# AuxiliaryPowerSupply.net
KiCad netlist of a schematic drawn in Altium Designer
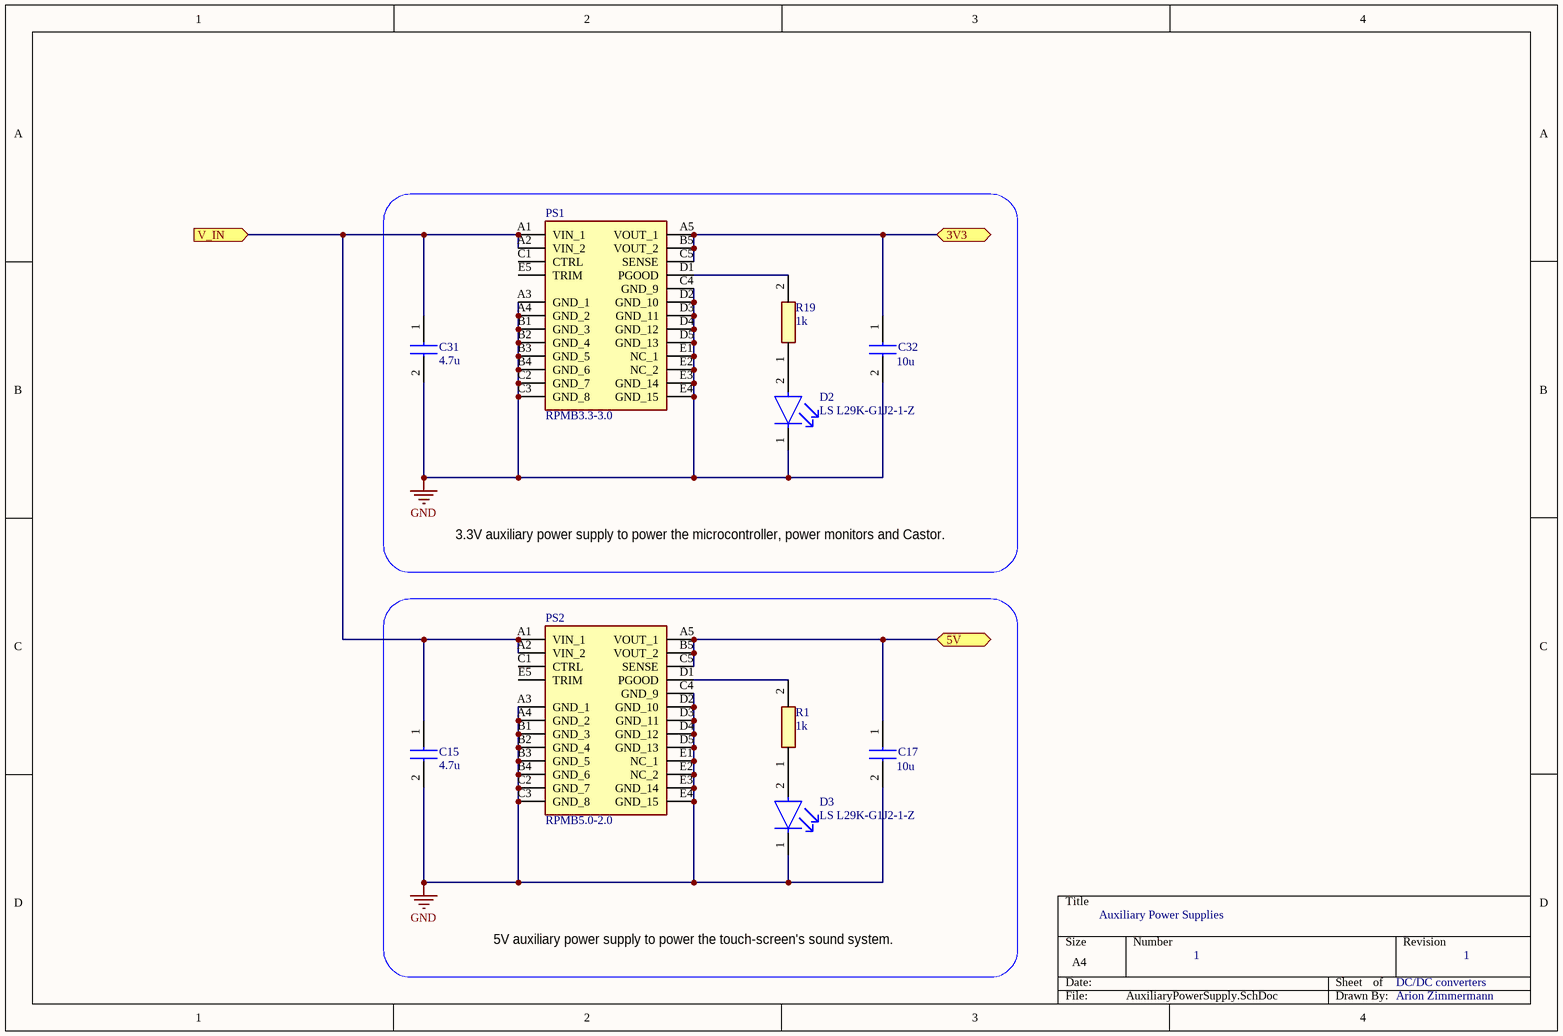
[diagram p0: AuxiliaryPowerSupply.SchDoc]

(export (version "E")
  (design (tool "Eeschema 10.0.6"))
  (components
    (comp (ref "C15")
      (value "4.7u")
      (footprint "SamacSys:CAPC5750X310N")
      (description "Capacitor")
      (fields
        (field (name "MANUFACTURER_PART_NUMBER") "C5750X7R2A475K230KA")
        (field (name "MOUSER PART NUMBER") "810-C5750X7R2A475K")
      )
      (libsource (lib "CarrierBoard") (part "C5750X7R2A475K230KA"))
    )
    (comp (ref "C17")
      (value "10u")
      (footprint "SamacSys:C1206")
      (description "Capacitor")
      (fields
        (field (name "MANUFACTURER_PART_NUMBER") "C1206C106K4RACTU")
        (field (name "MOUSER PART NUMBER") "80-C1206C106K4R")
      )
      (libsource (lib "SamacSys") (part "C1206C106K4RACTU"))
    )
    (comp (ref "C31")
      (value "4.7u")
      (footprint "SamacSys:CAPC5750X310N")
      (description "Capacitor")
      (fields
        (field (name "MANUFACTURER_PART_NUMBER") "C5750X7R2A475K230KA")
        (field (name "MOUSER PART NUMBER") "810-C5750X7R2A475K")
      )
      (libsource (lib "CarrierBoard") (part "C5750X7R2A475K230KA"))
    )
    (comp (ref "C32")
      (value "10u")
      (footprint "SamacSys:C1206")
      (description "Capacitor")
      (fields
        (field (name "MANUFACTURER_PART_NUMBER") "C1206C106K4RACTU")
        (field (name "MOUSER PART NUMBER") "80-C1206C106K4R")
      )
      (libsource (lib "SamacSys") (part "C1206C106K4RACTU"))
    )
    (comp (ref "D2")
      (value "LS L29K-G1J2-1-Z")
      (footprint "FP-LS_L29K-MFG")
      (description "LED RED DIFFUSED 0603 SMD")
      (fields
        (field (name "MANUFACTURER") "Osram Opto")
        (field (name "OCTOPART") "https://octopart.com/ls+l29k-g1j2-1-z-osram+opto-31093939")
      )
      (libsource (lib "Altium Content Vault") (part "8706943c75ba83719d021d2fdc84c58"))
    )
    (comp (ref "D3")
      (value "LS L29K-G1J2-1-Z")
      (footprint "FP-LS_L29K-MFG")
      (description "LED RED DIFFUSED 0603 SMD")
      (fields
        (field (name "MANUFACTURER") "Osram Opto")
        (field (name "OCTOPART") "https://octopart.com/ls+l29k-g1j2-1-z-osram+opto-31093939")
      )
      (libsource (lib "Altium Content Vault") (part "8706943c75ba83719d021d2fdc84c58"))
    )
    (comp (ref "PS1")
      (value "RPMB3.3-3.0")
      (footprint "CarrierBoard:RPMB5030")
      (description "Power Supply")
      (fields
        (field (name "MANUFACTURER_PART_NUMBER") "RPMB5.0-3.0")
        (field (name "MOUSER PART NUMBER") "919-RPMB5.0-3.0")
      )
      (libsource (lib "*") (part "RPMB5.0-3.0"))
    )
    (comp (ref "PS2")
      (value "RPMB5.0-2.0")
      (footprint "RPMB5020")
      (description "Power Supply")
      (libsource (lib "SamacSys") (part "RPMB5.0-2.0"))
    )
    (comp (ref "R1")
      (value "1k")
      (footprint "SamacSys:RESC1608X55N")
      (description "Resistor")
      (fields
        (field (name "MANUFACTURER_PART_NUMBER") "CRCW06031K00JNEAC")
        (field (name "MOUSER PART NUMBER") "71-CRCW06031K00JNEAC")
      )
      (libsource (lib "CarrierBoard") (part "CRCW06031K00JNEAC"))
    )
    (comp (ref "R19")
      (value "1k")
      (footprint "SamacSys:RESC1608X55N")
      (description "Resistor")
      (fields
        (field (name "MANUFACTURER_PART_NUMBER") "CRCW06031K00JNEAC")
        (field (name "MOUSER PART NUMBER") "71-CRCW06031K00JNEAC")
      )
      (libsource (lib "CarrierBoard") (part "CRCW06031K00JNEAC"))
    )
  )
  (nets
    (net (code "1") (name "/3V3") (class "Default")
      (node (ref "C32") (pin "1") (pinfunction "1_1") (pintype "passive"))
      (node (ref "PS1") (pin "A5") (pinfunction "VOUT_1_A5") (pintype "passive"))
      (node (ref "PS1") (pin "B5") (pinfunction "VOUT_2_B5") (pintype "passive"))
      (node (ref "PS1") (pin "C5") (pinfunction "SENSE_C5") (pintype "passive"))
    )
    (net (code "2") (name "/5V") (class "Default")
      (node (ref "C17") (pin "1") (pinfunction "1_1") (pintype "passive"))
      (node (ref "PS2") (pin "A5") (pinfunction "VOUT_1_A5") (pintype "passive"))
      (node (ref "PS2") (pin "B5") (pinfunction "VOUT_2_B5") (pintype "passive"))
      (node (ref "PS2") (pin "C5") (pinfunction "SENSE_C5") (pintype "passive"))
    )
    (net (code "3") (name "/V_IN") (class "Default")
      (node (ref "C15") (pin "1") (pinfunction "1_1") (pintype "passive"))
      (node (ref "C31") (pin "1") (pinfunction "1_1") (pintype "passive"))
      (node (ref "PS1") (pin "A1") (pinfunction "VIN_1_A1") (pintype "passive"))
      (node (ref "PS1") (pin "A2") (pinfunction "VIN_2_A2") (pintype "passive"))
      (node (ref "PS2") (pin "A1") (pinfunction "VIN_1_A1") (pintype "passive"))
      (node (ref "PS2") (pin "A2") (pinfunction "VIN_2_A2") (pintype "passive"))
    )
    (net (code "4") (name "GND") (class "Default")
      (node (ref "C15") (pin "2") (pinfunction "2_2") (pintype "passive"))
      (node (ref "C17") (pin "2") (pinfunction "2_2") (pintype "passive"))
      (node (ref "C31") (pin "2") (pinfunction "2_2") (pintype "passive"))
      (node (ref "C32") (pin "2") (pinfunction "2_2") (pintype "passive"))
      (node (ref "D2") (pin "1") (pinfunction "C_1") (pintype "passive"))
      (node (ref "D3") (pin "1") (pinfunction "C_1") (pintype "passive"))
      (node (ref "PS1") (pin "A3") (pinfunction "GND_1_A3") (pintype "passive"))
      (node (ref "PS1") (pin "A4") (pinfunction "GND_2_A4") (pintype "passive"))
      (node (ref "PS1") (pin "B1") (pinfunction "GND_3_B1") (pintype "passive"))
      (node (ref "PS1") (pin "B2") (pinfunction "GND_4_B2") (pintype "passive"))
      (node (ref "PS1") (pin "B3") (pinfunction "GND_5_B3") (pintype "passive"))
      (node (ref "PS1") (pin "B4") (pinfunction "GND_6_B4") (pintype "passive"))
      (node (ref "PS1") (pin "C2") (pinfunction "GND_7_C2") (pintype "passive"))
      (node (ref "PS1") (pin "C3") (pinfunction "GND_8_C3") (pintype "passive"))
      (node (ref "PS1") (pin "C4") (pinfunction "GND_9_C4") (pintype "passive"))
      (node (ref "PS1") (pin "D2") (pinfunction "GND_10_D2") (pintype "passive"))
      (node (ref "PS1") (pin "D3") (pinfunction "GND_11_D3") (pintype "passive"))
      (node (ref "PS1") (pin "D4") (pinfunction "GND_12_D4") (pintype "passive"))
      (node (ref "PS1") (pin "D5") (pinfunction "GND_13_D5") (pintype "passive"))
      (node (ref "PS1") (pin "E1") (pinfunction "NC_1_E1") (pintype "passive"))
      (node (ref "PS1") (pin "E2") (pinfunction "NC_2_E2") (pintype "passive"))
      (node (ref "PS1") (pin "E3") (pinfunction "GND_14_E3") (pintype "passive"))
      (node (ref "PS1") (pin "E4") (pinfunction "GND_15_E4") (pintype "passive"))
      (node (ref "PS2") (pin "A3") (pinfunction "GND_1_A3") (pintype "passive"))
      (node (ref "PS2") (pin "A4") (pinfunction "GND_2_A4") (pintype "passive"))
      (node (ref "PS2") (pin "B1") (pinfunction "GND_3_B1") (pintype "passive"))
      (node (ref "PS2") (pin "B2") (pinfunction "GND_4_B2") (pintype "passive"))
      (node (ref "PS2") (pin "B3") (pinfunction "GND_5_B3") (pintype "passive"))
      (node (ref "PS2") (pin "B4") (pinfunction "GND_6_B4") (pintype "passive"))
      (node (ref "PS2") (pin "C2") (pinfunction "GND_7_C2") (pintype "passive"))
      (node (ref "PS2") (pin "C3") (pinfunction "GND_8_C3") (pintype "passive"))
      (node (ref "PS2") (pin "C4") (pinfunction "GND_9_C4") (pintype "passive"))
      (node (ref "PS2") (pin "D2") (pinfunction "GND_10_D2") (pintype "passive"))
      (node (ref "PS2") (pin "D3") (pinfunction "GND_11_D3") (pintype "passive"))
      (node (ref "PS2") (pin "D4") (pinfunction "GND_12_D4") (pintype "passive"))
      (node (ref "PS2") (pin "D5") (pinfunction "GND_13_D5") (pintype "passive"))
      (node (ref "PS2") (pin "E1") (pinfunction "NC_1_E1") (pintype "passive"))
      (node (ref "PS2") (pin "E2") (pinfunction "NC_2_E2") (pintype "passive"))
      (node (ref "PS2") (pin "E3") (pinfunction "GND_14_E3") (pintype "passive"))
      (node (ref "PS2") (pin "E4") (pinfunction "GND_15_E4") (pintype "passive"))
    )
    (net (code "5") (name "Net-(D2-A)") (class "Default")
      (node (ref "D2") (pin "2") (pinfunction "A_2") (pintype "passive"))
      (node (ref "R19") (pin "1") (pinfunction "1_1") (pintype "passive"))
    )
    (net (code "6") (name "Net-(D3-A)") (class "Default")
      (node (ref "D3") (pin "2") (pinfunction "A_2") (pintype "passive"))
      (node (ref "R1") (pin "1") (pinfunction "1_1") (pintype "passive"))
    )
    (net (code "7") (name "Net-(PS1-PGOOD)") (class "Default")
      (node (ref "PS1") (pin "D1") (pinfunction "PGOOD_D1") (pintype "passive"))
      (node (ref "R19") (pin "2") (pinfunction "2_2") (pintype "passive"))
    )
    (net (code "8") (name "Net-(PS2-PGOOD)") (class "Default")
      (node (ref "PS2") (pin "D1") (pinfunction "PGOOD_D1") (pintype "passive"))
      (node (ref "R1") (pin "2") (pinfunction "2_2") (pintype "passive"))
    )
    (net (code "9") (name "unconnected-(PS1-CTRL-PadC1)") (class "Default")
      (node (ref "PS1") (pin "C1") (pinfunction "CTRL_C1") (pintype "passive"))
    )
    (net (code "10") (name "unconnected-(PS1-TRIM-PadE5)") (class "Default")
      (node (ref "PS1") (pin "E5") (pinfunction "TRIM_E5") (pintype "passive"))
    )
    (net (code "11") (name "unconnected-(PS2-CTRL-PadC1)") (class "Default")
      (node (ref "PS2") (pin "C1") (pinfunction "CTRL_C1") (pintype "passive"))
    )
    (net (code "12") (name "unconnected-(PS2-TRIM-PadE5)") (class "Default")
      (node (ref "PS2") (pin "E5") (pinfunction "TRIM_E5") (pintype "passive"))
    )
  )
)
